# Sheet2.net
KiCad netlist of a schematic drawn in Altium Designer
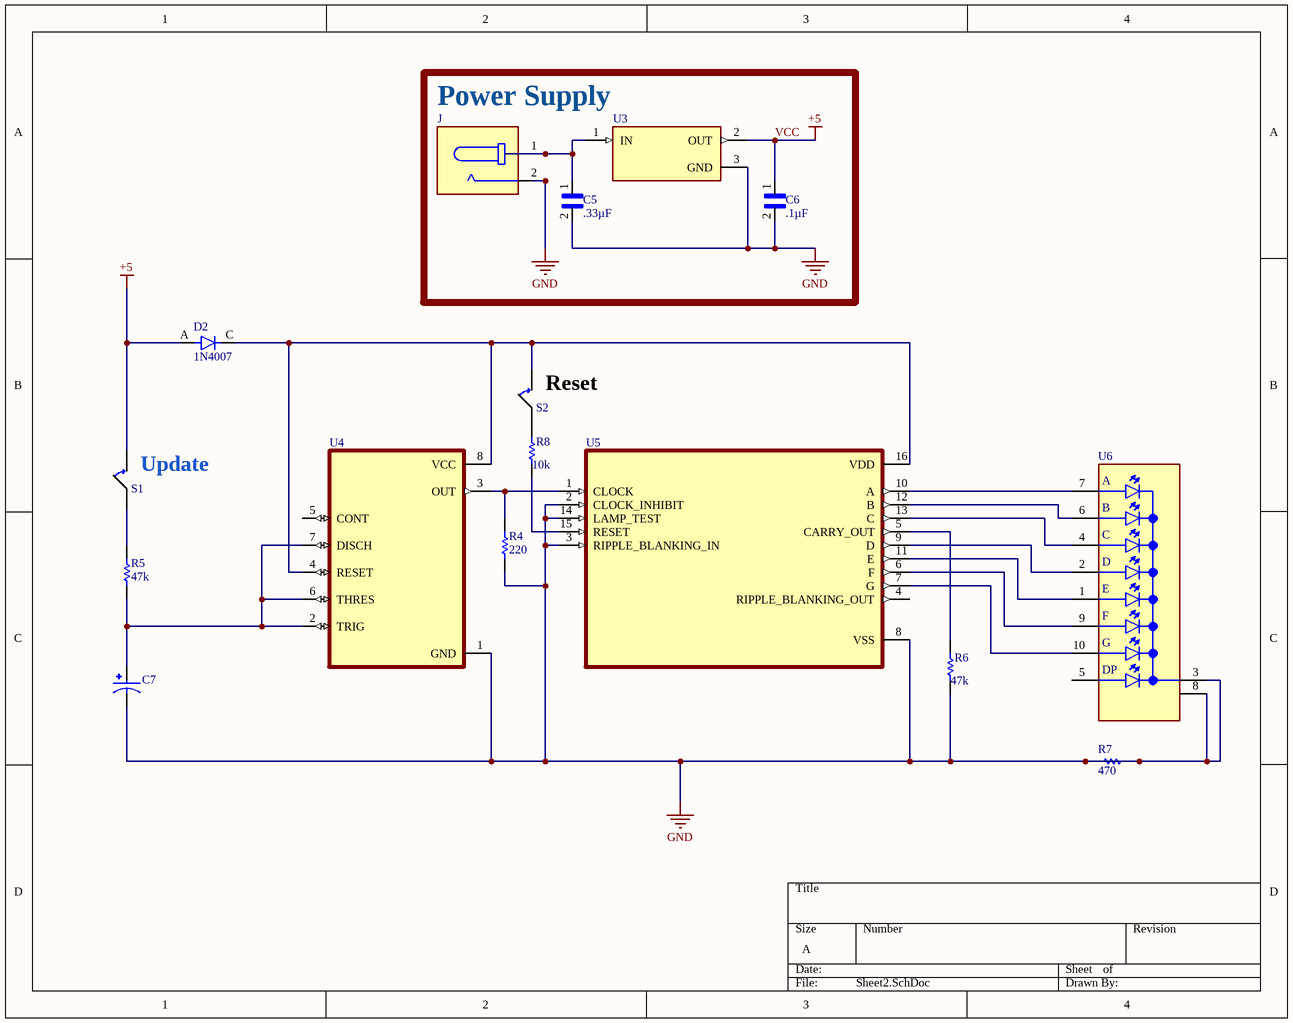
[diagram p0: Sheet2.SchDoc]

(export (version "E")
  (design (tool "Eeschema 10.0.6"))
  (components
    (comp (ref "C5")
      (value ".33µF")
      (footprint "CAPC3216X190N")
      (description "SMD Multilayer Ceramic Capacitor, GRM Series, 220 F, 20%, X5R, 6.3 V, 1206 [3216 Metric]")
      (fields (field (name "DIGI-KEY_PART_NUMBER") "490-13970-1-ND") (field (name "MP") "GRM31CR60J227ME11L"))
      (libsource (lib "GRM31CR60J227ME11L") (part "GRM31CR60J227ME11L"))
    )
    (comp (ref "C6")
      (value ".1µF")
      (footprint "CAPC3216X190N")
      (description "SMD Multilayer Ceramic Capacitor, GRM Series, 220 F, 20%, X5R, 6.3 V, 1206 [3216 Metric]")
      (fields (field (name "DIGI-KEY_PART_NUMBER") "490-13970-1-ND") (field (name "MP") "GRM31CR60J227ME11L"))
      (libsource (lib "GRM31CR60J227ME11L") (part "GRM31CR60J227ME11L"))
    )
    (comp (ref "C7")
      (value "EEUED2G100")
      (footprint "CAPPRD500W60D1000H2000")
      (description "10F 400V Aluminum Electrolytic Capacitors Radial, Can 8000 Hrs @ 105C")
      (fields (field (name "MF") "Panasonic Electronic") (field (name "MP") "EEU-ED2G100"))
      (libsource (lib "EEUED2G100") (part "EEUED2G100"))
    )
    (comp (ref "D2")
      (value "1N4007")
      (footprint "DIOAD1060W80L520D270")
      (description "Diode Standard 1000 V 1A Through Hole DO-41")
      (fields (field (name "MF") "NTE Electronics, Inc."))
      (libsource (lib "1N4007") (part "1N4007"))
    )
    (comp (ref "J")
      (value "PJ-037AH")
      (footprint "CUI_PJ-037AH")
      (description "2.0 x 6.5 mm, 5.0 A, Horizontal, Through Hole, Dc Power Jack Connector")
      (fields (field (name "MF") "CUI Devices"))
      (libsource (lib "PJ-037AH") (part "PJ-037AH"))
    )
    (comp (ref "R4")
      (value "220")
      (footprint "RES_ERJS03F1001V")
      (description "Resistor")
      (libsource (lib "Simulation Generic Components") (part "Resistor"))
    )
    (comp (ref "R5")
      (value "47k")
      (footprint "RES_ERJS03F1001V")
      (description "Resistor")
      (libsource (lib "Simulation Generic Components") (part "Resistor"))
    )
    (comp (ref "R6")
      (value "47k")
      (footprint "RES_ERJS03F1001V")
      (description "Resistor")
      (libsource (lib "Simulation Generic Components") (part "Resistor"))
    )
    (comp (ref "R7")
      (value "470")
      (footprint "RES_ERJS03F1001V")
      (description "Resistor")
      (libsource (lib "Simulation Generic Components") (part "Resistor"))
    )
    (comp (ref "R8")
      (value "10k")
      (footprint "RES_ERJS03F1001V")
      (description "Resistor")
      (libsource (lib "Simulation Generic Components") (part "Resistor"))
    )
    (comp (ref "S1")
      (value "Button Tactile Switch, NO 0.05 A 0.8mm")
      (footprint "Button8014X17N")
      (fields
        (field (name "MANUFACTURER") "C & K")
        (field (name "MANUFACTURER PART NO.") "B3F1000")
        (field (name "CREATOR") "R Kanjee")
      )
      (libsource (lib "Omron Tactile Switches") (part "Button Tactile Switch, NO 0.05 A 0.8mm"))
    )
    (comp (ref "S2")
      (value "Button Tactile Switch, NO 0.05 A 0.8mm")
      (footprint "Button8014X17N")
      (fields
        (field (name "MANUFACTURER") "C & K")
        (field (name "MANUFACTURER PART NO.") "B3F1000")
        (field (name "CREATOR") "R Kanjee")
      )
      (libsource (lib "Omron Tactile Switches") (part "Button Tactile Switch, NO 0.05 A 0.8mm"))
    )
    (comp (ref "U3")
      (value "7805CD2T")
      (footprint "TO254P1542X460-3N")
      (description "Linear Voltage Regulator IC Positive Fixed 1 Output 1.5A D2PAK")
      (fields (field (name "MF") "STMicroelectronics"))
      (libsource (lib "7805CD2T") (part "7805CD2T"))
    )
    (comp (ref "U4")
      (value "NE555PW")
      (footprint "SOP65P640X120-8N")
      (description "Single Precision Timer 8-TSSOP 0 to 70")
      (fields (field (name "MF") "Texas Instruments"))
      (libsource (lib "NE555PW") (part "NE555PW"))
    )
    (comp (ref "U5")
      (value "CD4033BE")
      (footprint "DIP794W45P254L1969H508Q16")
      (fields (field (name "MF") "Texas Instruments"))
      (libsource (lib "CD4033BE") (part "CD4033BE"))
    )
    (comp (ref "U6")
      (value "LDSC512RI")
      (footprint "LED_LDSC512RI")
      (fields (field (name "MF") "Lumex Optoelectronics"))
      (libsource (lib "LDSC512RI") (part "LDSC512RI"))
    )
  )
  (nets
    (net (code "1") (name "+5") (class "Default")
      (node (ref "C6") (pin "1") (pinfunction "1_1") (pintype "passive"))
      (node (ref "D2") (pin "A") (pinfunction "A_A") (pintype "passive"))
      (node (ref "S1") (pin "1") (pinfunction "1_1") (pintype "passive"))
      (node (ref "U3") (pin "2") (pinfunction "OUT_2") (pintype "output"))
    )
    (net (code "2") (name "GND") (class "Default")
      (node (ref "C5") (pin "2") (pinfunction "2_2") (pintype "passive"))
      (node (ref "C6") (pin "2") (pinfunction "2_2") (pintype "passive"))
      (node (ref "C7") (pin "N") (pinfunction "N_N") (pintype "passive"))
      (node (ref "J") (pin "2") (pinfunction "2_2") (pintype "passive"))
      (node (ref "R4") (pin "1") (pinfunction "1_1") (pintype "passive"))
      (node (ref "R6") (pin "1") (pinfunction "1_1") (pintype "passive"))
      (node (ref "R7") (pin "1") (pinfunction "1_1") (pintype "passive"))
      (node (ref "R7") (pin "2") (pinfunction "2_2") (pintype "passive"))
      (node (ref "U3") (pin "3") (pinfunction "GND_3") (pintype "power_in"))
      (node (ref "U4") (pin "1") (pinfunction "GND_1") (pintype "power_in"))
      (node (ref "U5") (pin "14") (pinfunction "LAMP_TEST_14") (pintype "input"))
      (node (ref "U5") (pin "2") (pinfunction "CLOCK_INHIBIT_2") (pintype "input"))
      (node (ref "U5") (pin "3") (pinfunction "RIPPLE_BLANKING_IN_3") (pintype "input"))
      (node (ref "U5") (pin "8") (pinfunction "VSS_8") (pintype "power_in"))
      (node (ref "U6") (pin "3") (pinfunction "CC_3") (pintype "passive"))
      (node (ref "U6") (pin "8") (pinfunction "CC_8") (pintype "passive"))
    )
    (net (code "3") (name "Net-(R5-Pad2)") (class "Default")
      (node (ref "R5") (pin "2") (pinfunction "2_2") (pintype "passive"))
      (node (ref "S1") (pin "1") (pinfunction "1_1") (pintype "passive"))
    )
    (net (code "4") (name "Net-(U3-IN)") (class "Default")
      (node (ref "C5") (pin "1") (pinfunction "1_1") (pintype "passive"))
      (node (ref "J") (pin "1") (pinfunction "1_1") (pintype "passive"))
      (node (ref "U3") (pin "1") (pinfunction "IN_1") (pintype "input"))
    )
    (net (code "5") (name "Net-(U4-DISCH)") (class "Default")
      (node (ref "C7") (pin "P") (pinfunction "P_P") (pintype "passive"))
      (node (ref "R5") (pin "1") (pinfunction "1_1") (pintype "passive"))
      (node (ref "U4") (pin "2") (pinfunction "TRIG_2") (pintype "bidirectional"))
      (node (ref "U4") (pin "6") (pinfunction "THRES_6") (pintype "bidirectional"))
      (node (ref "U4") (pin "7") (pinfunction "DISCH_7") (pintype "bidirectional"))
    )
    (net (code "6") (name "Net-(U4-OUT)") (class "Default")
      (node (ref "R4") (pin "2") (pinfunction "2_2") (pintype "passive"))
      (node (ref "U4") (pin "3") (pinfunction "OUT_3") (pintype "output"))
      (node (ref "U5") (pin "1") (pinfunction "CLOCK_1") (pintype "input"))
    )
    (net (code "7") (name "Net-(U4-RESET)") (class "Default")
      (node (ref "D2") (pin "C") (pinfunction "C_C") (pintype "passive"))
      (node (ref "S2") (pin "1") (pinfunction "1_1") (pintype "passive"))
      (node (ref "U4") (pin "4") (pinfunction "RESET_4") (pintype "bidirectional"))
      (node (ref "U4") (pin "8") (pinfunction "VCC_8") (pintype "power_in"))
      (node (ref "U5") (pin "16") (pinfunction "VDD_16") (pintype "power_in"))
    )
    (net (code "8") (name "Net-(U5-A)") (class "Default")
      (node (ref "U5") (pin "10") (pinfunction "A_10") (pintype "output"))
      (node (ref "U6") (pin "7") (pinfunction "A_7") (pintype "passive"))
    )
    (net (code "9") (name "Net-(U5-B)") (class "Default")
      (node (ref "U5") (pin "12") (pinfunction "B_12") (pintype "output"))
      (node (ref "U6") (pin "6") (pinfunction "B_6") (pintype "passive"))
    )
    (net (code "10") (name "Net-(U5-C)") (class "Default")
      (node (ref "U5") (pin "13") (pinfunction "C_13") (pintype "output"))
      (node (ref "U6") (pin "4") (pinfunction "C_4") (pintype "passive"))
    )
    (net (code "11") (name "Net-(U5-CARRY_OUT)") (class "Default")
      (node (ref "R6") (pin "2") (pinfunction "2_2") (pintype "passive"))
      (node (ref "U5") (pin "5") (pinfunction "CARRY_OUT_5") (pintype "output"))
    )
    (net (code "12") (name "Net-(U5-D)") (class "Default")
      (node (ref "U5") (pin "9") (pinfunction "D_9") (pintype "output"))
      (node (ref "U6") (pin "2") (pinfunction "D_2") (pintype "passive"))
    )
    (net (code "13") (name "Net-(U5-E)") (class "Default")
      (node (ref "U5") (pin "11") (pinfunction "E_11") (pintype "output"))
      (node (ref "U6") (pin "1") (pinfunction "E_1") (pintype "passive"))
    )
    (net (code "14") (name "Net-(U5-F)") (class "Default")
      (node (ref "U5") (pin "6") (pinfunction "F_6") (pintype "output"))
      (node (ref "U6") (pin "9") (pinfunction "F_9") (pintype "passive"))
    )
    (net (code "15") (name "Net-(U5-G)") (class "Default")
      (node (ref "U5") (pin "7") (pinfunction "G_7") (pintype "output"))
      (node (ref "U6") (pin "10") (pinfunction "G_10") (pintype "passive"))
    )
    (net (code "16") (name "Net-(U5-RESET)") (class "Default")
      (node (ref "R8") (pin "1") (pinfunction "1_1") (pintype "passive"))
      (node (ref "U5") (pin "15") (pinfunction "RESET_15") (pintype "input"))
    )
    (net (code "17") (name "unconnected-(R8-Pad2)") (class "Default")
      (node (ref "R8") (pin "2") (pinfunction "2_2") (pintype "passive"))
    )
    (net (code "18") (name "unconnected-(S2-Pad1)") (class "Default")
      (node (ref "S2") (pin "1") (pinfunction "1_1") (pintype "passive"))
    )
    (net (code "19") (name "unconnected-(U4-CONT-Pad5)") (class "Default")
      (node (ref "U4") (pin "5") (pinfunction "CONT_5") (pintype "bidirectional"))
    )
    (net (code "20") (name "unconnected-(U5-RIPPLE_BLANKING_OUT-Pad4)") (class "Default")
      (node (ref "U5") (pin "4") (pinfunction "RIPPLE_BLANKING_OUT_4") (pintype "output"))
    )
    (net (code "21") (name "unconnected-(U6-DP-Pad5)") (class "Default")
      (node (ref "U6") (pin "5") (pinfunction "DP_5") (pintype "passive"))
    )
  )
)
